# MainPromSignController.net
KiCad netlist of a schematic drawn in EAGLE
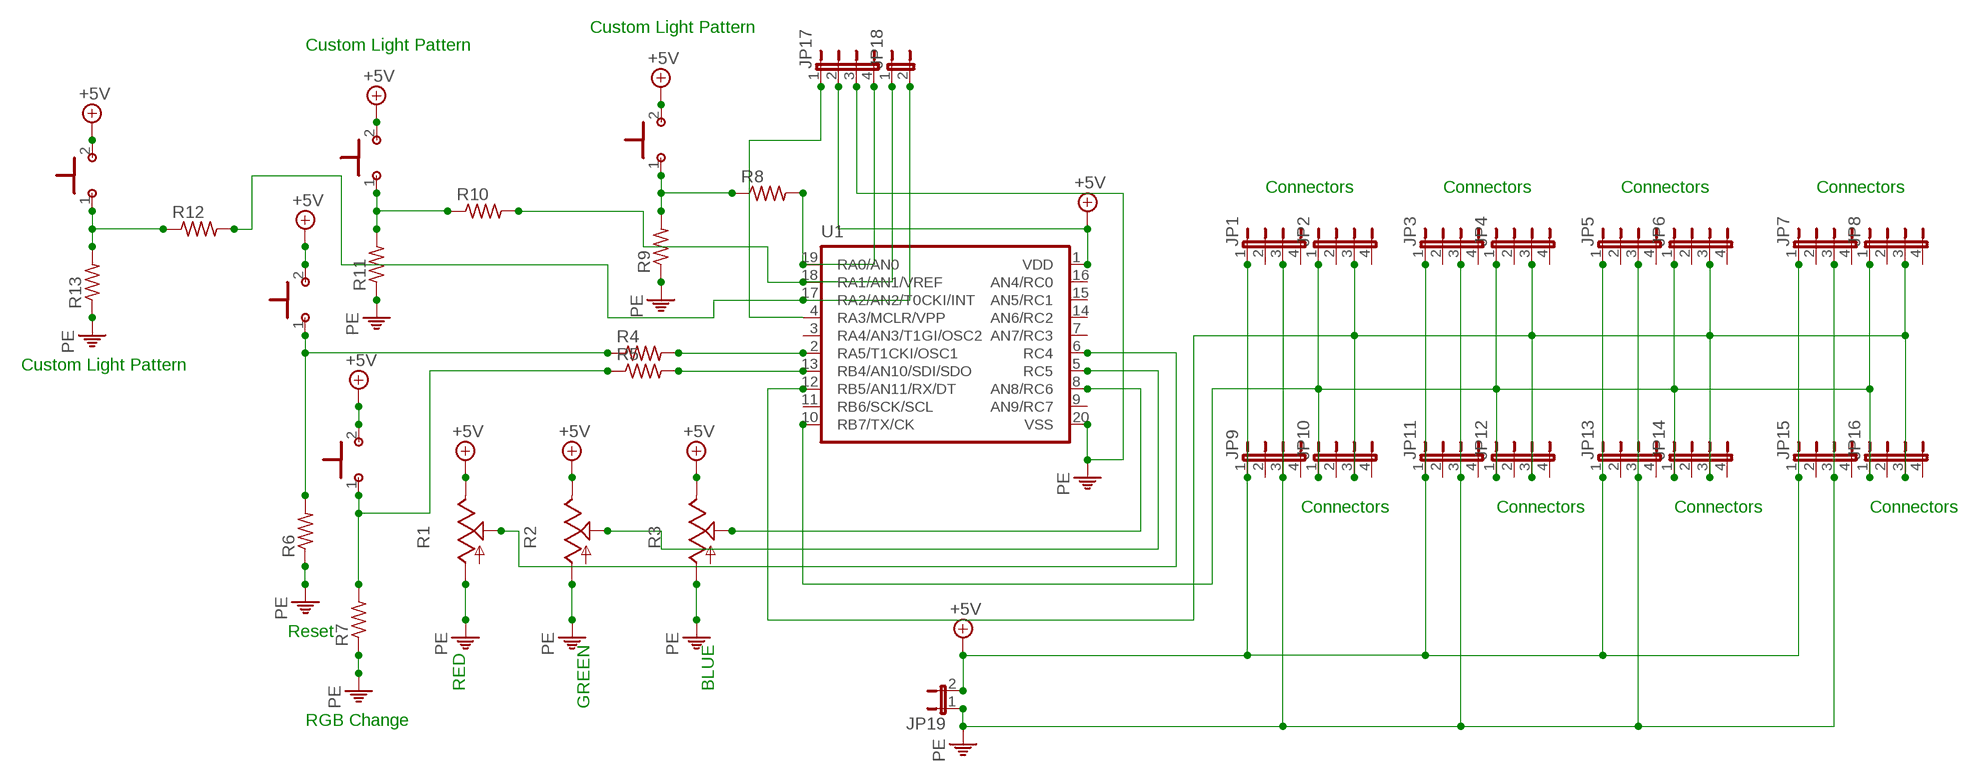
[diagram p0: schematic, sheet 1]

(export (version "E")
  (design (tool "Eeschema 10.0.6"))
  (components
    (comp (ref "JP1")
      (value "JP4E")
      (footprint "eagle-import:JP4")
      (libsource (lib "eagle-import") (part "JP4E"))
    )
    (comp (ref "JP2")
      (value "JP4E")
      (footprint "eagle-import:JP4")
      (libsource (lib "eagle-import") (part "JP4E"))
    )
    (comp (ref "JP3")
      (value "JP4E")
      (footprint "eagle-import:JP4")
      (libsource (lib "eagle-import") (part "JP4E"))
    )
    (comp (ref "JP4")
      (value "JP4E")
      (footprint "eagle-import:JP4")
      (libsource (lib "eagle-import") (part "JP4E"))
    )
    (comp (ref "JP5")
      (value "JP4E")
      (footprint "eagle-import:JP4")
      (libsource (lib "eagle-import") (part "JP4E"))
    )
    (comp (ref "JP6")
      (value "JP4E")
      (footprint "eagle-import:JP4")
      (libsource (lib "eagle-import") (part "JP4E"))
    )
    (comp (ref "JP7")
      (value "JP4E")
      (footprint "eagle-import:JP4")
      (libsource (lib "eagle-import") (part "JP4E"))
    )
    (comp (ref "JP8")
      (value "JP4E")
      (footprint "eagle-import:JP4")
      (libsource (lib "eagle-import") (part "JP4E"))
    )
    (comp (ref "JP9")
      (value "JP4E")
      (footprint "eagle-import:JP4")
      (libsource (lib "eagle-import") (part "JP4E"))
    )
    (comp (ref "JP10")
      (value "JP4E")
      (footprint "eagle-import:JP4")
      (libsource (lib "eagle-import") (part "JP4E"))
    )
    (comp (ref "JP11")
      (value "JP4E")
      (footprint "eagle-import:JP4")
      (libsource (lib "eagle-import") (part "JP4E"))
    )
    (comp (ref "JP12")
      (value "JP4E")
      (footprint "eagle-import:JP4")
      (libsource (lib "eagle-import") (part "JP4E"))
    )
    (comp (ref "JP13")
      (value "JP4E")
      (footprint "eagle-import:JP4")
      (libsource (lib "eagle-import") (part "JP4E"))
    )
    (comp (ref "JP14")
      (value "JP4E")
      (footprint "eagle-import:JP4")
      (libsource (lib "eagle-import") (part "JP4E"))
    )
    (comp (ref "JP15")
      (value "JP4E")
      (footprint "eagle-import:JP4")
      (libsource (lib "eagle-import") (part "JP4E"))
    )
    (comp (ref "JP16")
      (value "JP4E")
      (footprint "eagle-import:JP4")
      (libsource (lib "eagle-import") (part "JP4E"))
    )
    (comp (ref "JP17")
      (value "JP4E")
      (footprint "eagle-import:JP4")
      (libsource (lib "eagle-import") (part "JP4E"))
    )
    (comp (ref "JP18")
      (value "JP1E")
      (footprint "eagle-import:JP1")
      (libsource (lib "eagle-import") (part "JP1E"))
    )
    (comp (ref "JP19")
      (value "JP1E")
      (footprint "eagle-import:JP1")
      (libsource (lib "eagle-import") (part "JP1E"))
    )
    (comp (ref "R1")
      (value "TRIM_US-B25P")
      (footprint "eagle-import:B25P")
      (libsource (lib "eagle-import") (part "TRIM_US-B25P"))
    )
    (comp (ref "R2")
      (value "TRIM_US-B25P")
      (footprint "eagle-import:B25P")
      (libsource (lib "eagle-import") (part "TRIM_US-B25P"))
    )
    (comp (ref "R3")
      (value "TRIM_US-B25P")
      (footprint "eagle-import:B25P")
      (libsource (lib "eagle-import") (part "TRIM_US-B25P"))
    )
    (comp (ref "R4")
      (value "R-US_0207/10")
      (footprint "eagle-import:0207_10")
      (libsource (lib "eagle-import") (part "R-US_0207/10"))
    )
    (comp (ref "R5")
      (value "R-US_0207/10")
      (footprint "eagle-import:0207_10")
      (libsource (lib "eagle-import") (part "R-US_0207/10"))
    )
    (comp (ref "R6")
      (value "R-US_0207/10")
      (footprint "eagle-import:0207_10")
      (libsource (lib "eagle-import") (part "R-US_0207/10"))
    )
    (comp (ref "R7")
      (value "R-US_0207/10")
      (footprint "eagle-import:0207_10")
      (libsource (lib "eagle-import") (part "R-US_0207/10"))
    )
    (comp (ref "R8")
      (value "R-US_0207/10")
      (footprint "eagle-import:0207_10")
      (libsource (lib "eagle-import") (part "R-US_0207/10"))
    )
    (comp (ref "R9")
      (value "R-US_0207/10")
      (footprint "eagle-import:0207_10")
      (libsource (lib "eagle-import") (part "R-US_0207/10"))
    )
    (comp (ref "R10")
      (value "R-US_0207/10")
      (footprint "eagle-import:0207_10")
      (libsource (lib "eagle-import") (part "R-US_0207/10"))
    )
    (comp (ref "R11")
      (value "R-US_0207/10")
      (footprint "eagle-import:0207_10")
      (libsource (lib "eagle-import") (part "R-US_0207/10"))
    )
    (comp (ref "R12")
      (value "R-US_0207/10")
      (footprint "eagle-import:0207_10")
      (libsource (lib "eagle-import") (part "R-US_0207/10"))
    )
    (comp (ref "R13")
      (value "R-US_0207/10")
      (footprint "eagle-import:0207_10")
      (libsource (lib "eagle-import") (part "R-US_0207/10"))
    )
    (comp (ref "U$1")
      (value "PUSHBUTTON")
      (footprint "eagle-import:PUSHBUTTON")
      (libsource (lib "eagle-import") (part "PUSHBUTTON"))
    )
    (comp (ref "U$2")
      (value "PUSHBUTTON")
      (footprint "eagle-import:PUSHBUTTON")
      (libsource (lib "eagle-import") (part "PUSHBUTTON"))
    )
    (comp (ref "U$3")
      (value "PUSHBUTTON")
      (footprint "eagle-import:PUSHBUTTON")
      (libsource (lib "eagle-import") (part "PUSHBUTTON"))
    )
    (comp (ref "U$4")
      (value "PUSHBUTTON")
      (footprint "eagle-import:PUSHBUTTON")
      (libsource (lib "eagle-import") (part "PUSHBUTTON"))
    )
    (comp (ref "U$5")
      (value "PUSHBUTTON")
      (footprint "eagle-import:PUSHBUTTON")
      (libsource (lib "eagle-import") (part "PUSHBUTTON"))
    )
    (comp (ref "U1")
      (value "PIC16F6XX")
      (footprint "eagle-import:DIL20")
      (libsource (lib "eagle-import") (part "PIC16F6XX"))
    )
  )
  (nets
    (net (code "1") (name "+5V") (class "Default")
      (node (ref "JP1") (pin "1") (pinfunction "1_1") (pintype "passive"))
      (node (ref "JP11") (pin "1") (pinfunction "1_1") (pintype "passive"))
      (node (ref "JP13") (pin "1") (pinfunction "1_1") (pintype "passive"))
      (node (ref "JP15") (pin "1") (pinfunction "1_1") (pintype "passive"))
      (node (ref "JP17") (pin "2") (pinfunction "2_2") (pintype "passive"))
      (node (ref "JP19") (pin "2") (pinfunction "2_2") (pintype "passive"))
      (node (ref "JP3") (pin "1") (pinfunction "1_1") (pintype "passive"))
      (node (ref "JP5") (pin "1") (pinfunction "1_1") (pintype "passive"))
      (node (ref "JP7") (pin "1") (pinfunction "1_1") (pintype "passive"))
      (node (ref "JP9") (pin "1") (pinfunction "1_1") (pintype "passive"))
      (node (ref "R1") (pin "E") (pinfunction "E_E") (pintype "passive"))
      (node (ref "R2") (pin "E") (pinfunction "E_E") (pintype "passive"))
      (node (ref "R3") (pin "E") (pinfunction "E_E") (pintype "passive"))
      (node (ref "U$1") (pin "2") (pinfunction "2_2") (pintype "bidirectional"))
      (node (ref "U$2") (pin "2") (pinfunction "2_2") (pintype "bidirectional"))
      (node (ref "U$3") (pin "2") (pinfunction "2_2") (pintype "bidirectional"))
      (node (ref "U$4") (pin "2") (pinfunction "2_2") (pintype "bidirectional"))
      (node (ref "U$5") (pin "2") (pinfunction "2_2") (pintype "bidirectional"))
      (node (ref "U1") (pin "1") (pinfunction "VDD_1") (pintype "power_in"))
    )
    (net (code "2") (name "Net-(R4-Pad1)") (class "Default")
      (node (ref "R4") (pin "1") (pinfunction "1_1") (pintype "passive"))
      (node (ref "R6") (pin "2") (pinfunction "2_2") (pintype "passive"))
      (node (ref "U$1") (pin "1") (pinfunction "1_1") (pintype "bidirectional"))
    )
    (net (code "3") (name "Net-(R5-Pad1)") (class "Default")
      (node (ref "R5") (pin "1") (pinfunction "1_1") (pintype "passive"))
      (node (ref "R7") (pin "2") (pinfunction "2_2") (pintype "passive"))
      (node (ref "U$2") (pin "1") (pinfunction "1_1") (pintype "bidirectional"))
    )
    (net (code "4") (name "Net-(R8-Pad1)") (class "Default")
      (node (ref "R8") (pin "1") (pinfunction "1_1") (pintype "passive"))
      (node (ref "R9") (pin "2") (pinfunction "2_2") (pintype "passive"))
      (node (ref "U$3") (pin "1") (pinfunction "1_1") (pintype "bidirectional"))
    )
    (net (code "5") (name "Net-(R10-Pad1)") (class "Default")
      (node (ref "R10") (pin "1") (pinfunction "1_1") (pintype "passive"))
      (node (ref "R11") (pin "2") (pinfunction "2_2") (pintype "passive"))
      (node (ref "U$4") (pin "1") (pinfunction "1_1") (pintype "bidirectional"))
    )
    (net (code "6") (name "Net-(R12-Pad1)") (class "Default")
      (node (ref "R12") (pin "1") (pinfunction "1_1") (pintype "passive"))
      (node (ref "R13") (pin "2") (pinfunction "2_2") (pintype "passive"))
      (node (ref "U$5") (pin "1") (pinfunction "1_1") (pintype "bidirectional"))
    )
    (net (code "7") (name "Net-(U1-AN8{slash}RC6)") (class "Default")
      (node (ref "R3") (pin "S") (pinfunction "S_S") (pintype "passive"))
      (node (ref "U1") (pin "8") (pinfunction "AN8/RC6_8") (pintype "bidirectional"))
    )
    (net (code "8") (name "Net-(U1-RA0{slash}AN0)") (class "Default")
      (node (ref "JP17") (pin "4") (pinfunction "4_4") (pintype "passive"))
      (node (ref "R8") (pin "2") (pinfunction "2_2") (pintype "passive"))
      (node (ref "U1") (pin "19") (pinfunction "RA0/AN0_19") (pintype "bidirectional"))
    )
    (net (code "9") (name "Net-(U1-RA1{slash}AN1{slash}VREF)") (class "Default")
      (node (ref "JP18") (pin "1") (pinfunction "1_1") (pintype "passive"))
      (node (ref "R10") (pin "2") (pinfunction "2_2") (pintype "passive"))
      (node (ref "U1") (pin "18") (pinfunction "RA1/AN1/VREF_18") (pintype "bidirectional"))
    )
    (net (code "10") (name "Net-(U1-RA2{slash}AN2{slash}T0CKI{slash}INT)") (class "Default")
      (node (ref "JP18") (pin "2") (pinfunction "2_2") (pintype "passive"))
      (node (ref "R12") (pin "2") (pinfunction "2_2") (pintype "passive"))
      (node (ref "U1") (pin "17") (pinfunction "RA2/AN2/T0CKI/INT_17") (pintype "bidirectional"))
    )
    (net (code "11") (name "Net-(U1-RA3{slash}MCLR{slash}VPP)") (class "Default")
      (node (ref "JP17") (pin "1") (pinfunction "1_1") (pintype "passive"))
      (node (ref "U1") (pin "4") (pinfunction "RA3/MCLR/VPP_4") (pintype "input"))
    )
    (net (code "12") (name "Net-(U1-RA5{slash}T1CKI{slash}OSC1)") (class "Default")
      (node (ref "R4") (pin "2") (pinfunction "2_2") (pintype "passive"))
      (node (ref "U1") (pin "2") (pinfunction "RA5/T1CKI/OSC1_2") (pintype "bidirectional"))
    )
    (net (code "13") (name "Net-(U1-RB4{slash}AN10{slash}SDI{slash}SDO)") (class "Default")
      (node (ref "R5") (pin "2") (pinfunction "2_2") (pintype "passive"))
      (node (ref "U1") (pin "13") (pinfunction "RB4/AN10/SDI/SDO_13") (pintype "bidirectional"))
    )
    (net (code "14") (name "Net-(U1-RB5{slash}AN11{slash}RX{slash}DT)") (class "Default")
      (node (ref "JP10") (pin "3") (pinfunction "3_3") (pintype "passive"))
      (node (ref "JP12") (pin "3") (pinfunction "3_3") (pintype "passive"))
      (node (ref "JP14") (pin "3") (pinfunction "3_3") (pintype "passive"))
      (node (ref "JP16") (pin "3") (pinfunction "3_3") (pintype "passive"))
      (node (ref "JP2") (pin "3") (pinfunction "3_3") (pintype "passive"))
      (node (ref "JP4") (pin "3") (pinfunction "3_3") (pintype "passive"))
      (node (ref "JP6") (pin "3") (pinfunction "3_3") (pintype "passive"))
      (node (ref "JP8") (pin "3") (pinfunction "3_3") (pintype "passive"))
      (node (ref "U1") (pin "12") (pinfunction "RB5/AN11/RX/DT_12") (pintype "bidirectional"))
    )
    (net (code "15") (name "Net-(U1-RB7{slash}TX{slash}CK)") (class "Default")
      (node (ref "JP10") (pin "1") (pinfunction "1_1") (pintype "passive"))
      (node (ref "JP12") (pin "1") (pinfunction "1_1") (pintype "passive"))
      (node (ref "JP14") (pin "1") (pinfunction "1_1") (pintype "passive"))
      (node (ref "JP16") (pin "1") (pinfunction "1_1") (pintype "passive"))
      (node (ref "JP2") (pin "1") (pinfunction "1_1") (pintype "passive"))
      (node (ref "JP4") (pin "1") (pinfunction "1_1") (pintype "passive"))
      (node (ref "JP6") (pin "1") (pinfunction "1_1") (pintype "passive"))
      (node (ref "JP8") (pin "1") (pinfunction "1_1") (pintype "passive"))
      (node (ref "U1") (pin "10") (pinfunction "RB7/TX/CK_10") (pintype "bidirectional"))
    )
    (net (code "16") (name "Net-(U1-RC4)") (class "Default")
      (node (ref "R1") (pin "S") (pinfunction "S_S") (pintype "passive"))
      (node (ref "U1") (pin "6") (pinfunction "RC4_6") (pintype "bidirectional"))
    )
    (net (code "17") (name "Net-(U1-RC5)") (class "Default")
      (node (ref "R2") (pin "S") (pinfunction "S_S") (pintype "passive"))
      (node (ref "U1") (pin "5") (pinfunction "RC5_5") (pintype "bidirectional"))
    )
    (net (code "18") (name "PE") (class "Default")
      (node (ref "JP1") (pin "3") (pinfunction "3_3") (pintype "passive"))
      (node (ref "JP11") (pin "3") (pinfunction "3_3") (pintype "passive"))
      (node (ref "JP13") (pin "3") (pinfunction "3_3") (pintype "passive"))
      (node (ref "JP15") (pin "3") (pinfunction "3_3") (pintype "passive"))
      (node (ref "JP17") (pin "3") (pinfunction "3_3") (pintype "passive"))
      (node (ref "JP19") (pin "1") (pinfunction "1_1") (pintype "passive"))
      (node (ref "JP3") (pin "3") (pinfunction "3_3") (pintype "passive"))
      (node (ref "JP5") (pin "3") (pinfunction "3_3") (pintype "passive"))
      (node (ref "JP7") (pin "3") (pinfunction "3_3") (pintype "passive"))
      (node (ref "JP9") (pin "3") (pinfunction "3_3") (pintype "passive"))
      (node (ref "R1") (pin "A") (pinfunction "A_A") (pintype "passive"))
      (node (ref "R11") (pin "1") (pinfunction "1_1") (pintype "passive"))
      (node (ref "R13") (pin "1") (pinfunction "1_1") (pintype "passive"))
      (node (ref "R2") (pin "A") (pinfunction "A_A") (pintype "passive"))
      (node (ref "R3") (pin "A") (pinfunction "A_A") (pintype "passive"))
      (node (ref "R6") (pin "1") (pinfunction "1_1") (pintype "passive"))
      (node (ref "R7") (pin "1") (pinfunction "1_1") (pintype "passive"))
      (node (ref "R9") (pin "1") (pinfunction "1_1") (pintype "passive"))
      (node (ref "U1") (pin "20") (pinfunction "VSS_20") (pintype "power_in"))
    )
    (net (code "19") (name "unconnected-(JP1-Pad2)") (class "Default")
      (node (ref "JP1") (pin "2") (pinfunction "2_2") (pintype "passive"))
    )
    (net (code "20") (name "unconnected-(JP1-Pad4)") (class "Default")
      (node (ref "JP1") (pin "4") (pinfunction "4_4") (pintype "passive"))
    )
    (net (code "21") (name "unconnected-(JP2-Pad2)") (class "Default")
      (node (ref "JP2") (pin "2") (pinfunction "2_2") (pintype "passive"))
    )
    (net (code "22") (name "unconnected-(JP2-Pad4)") (class "Default")
      (node (ref "JP2") (pin "4") (pinfunction "4_4") (pintype "passive"))
    )
    (net (code "23") (name "unconnected-(JP3-Pad2)") (class "Default")
      (node (ref "JP3") (pin "2") (pinfunction "2_2") (pintype "passive"))
    )
    (net (code "24") (name "unconnected-(JP3-Pad4)") (class "Default")
      (node (ref "JP3") (pin "4") (pinfunction "4_4") (pintype "passive"))
    )
    (net (code "25") (name "unconnected-(JP4-Pad2)") (class "Default")
      (node (ref "JP4") (pin "2") (pinfunction "2_2") (pintype "passive"))
    )
    (net (code "26") (name "unconnected-(JP4-Pad4)") (class "Default")
      (node (ref "JP4") (pin "4") (pinfunction "4_4") (pintype "passive"))
    )
    (net (code "27") (name "unconnected-(JP5-Pad2)") (class "Default")
      (node (ref "JP5") (pin "2") (pinfunction "2_2") (pintype "passive"))
    )
    (net (code "28") (name "unconnected-(JP5-Pad4)") (class "Default")
      (node (ref "JP5") (pin "4") (pinfunction "4_4") (pintype "passive"))
    )
    (net (code "29") (name "unconnected-(JP6-Pad2)") (class "Default")
      (node (ref "JP6") (pin "2") (pinfunction "2_2") (pintype "passive"))
    )
    (net (code "30") (name "unconnected-(JP6-Pad4)") (class "Default")
      (node (ref "JP6") (pin "4") (pinfunction "4_4") (pintype "passive"))
    )
    (net (code "31") (name "unconnected-(JP7-Pad2)") (class "Default")
      (node (ref "JP7") (pin "2") (pinfunction "2_2") (pintype "passive"))
    )
    (net (code "32") (name "unconnected-(JP7-Pad4)") (class "Default")
      (node (ref "JP7") (pin "4") (pinfunction "4_4") (pintype "passive"))
    )
    (net (code "33") (name "unconnected-(JP8-Pad2)") (class "Default")
      (node (ref "JP8") (pin "2") (pinfunction "2_2") (pintype "passive"))
    )
    (net (code "34") (name "unconnected-(JP8-Pad4)") (class "Default")
      (node (ref "JP8") (pin "4") (pinfunction "4_4") (pintype "passive"))
    )
    (net (code "35") (name "unconnected-(JP9-Pad2)") (class "Default")
      (node (ref "JP9") (pin "2") (pinfunction "2_2") (pintype "passive"))
    )
    (net (code "36") (name "unconnected-(JP9-Pad4)") (class "Default")
      (node (ref "JP9") (pin "4") (pinfunction "4_4") (pintype "passive"))
    )
    (net (code "37") (name "unconnected-(JP10-Pad2)") (class "Default")
      (node (ref "JP10") (pin "2") (pinfunction "2_2") (pintype "passive"))
    )
    (net (code "38") (name "unconnected-(JP10-Pad4)") (class "Default")
      (node (ref "JP10") (pin "4") (pinfunction "4_4") (pintype "passive"))
    )
    (net (code "39") (name "unconnected-(JP11-Pad2)") (class "Default")
      (node (ref "JP11") (pin "2") (pinfunction "2_2") (pintype "passive"))
    )
    (net (code "40") (name "unconnected-(JP11-Pad4)") (class "Default")
      (node (ref "JP11") (pin "4") (pinfunction "4_4") (pintype "passive"))
    )
    (net (code "41") (name "unconnected-(JP12-Pad2)") (class "Default")
      (node (ref "JP12") (pin "2") (pinfunction "2_2") (pintype "passive"))
    )
    (net (code "42") (name "unconnected-(JP12-Pad4)") (class "Default")
      (node (ref "JP12") (pin "4") (pinfunction "4_4") (pintype "passive"))
    )
    (net (code "43") (name "unconnected-(JP13-Pad2)") (class "Default")
      (node (ref "JP13") (pin "2") (pinfunction "2_2") (pintype "passive"))
    )
    (net (code "44") (name "unconnected-(JP13-Pad4)") (class "Default")
      (node (ref "JP13") (pin "4") (pinfunction "4_4") (pintype "passive"))
    )
    (net (code "45") (name "unconnected-(JP14-Pad2)") (class "Default")
      (node (ref "JP14") (pin "2") (pinfunction "2_2") (pintype "passive"))
    )
    (net (code "46") (name "unconnected-(JP14-Pad4)") (class "Default")
      (node (ref "JP14") (pin "4") (pinfunction "4_4") (pintype "passive"))
    )
    (net (code "47") (name "unconnected-(JP15-Pad2)") (class "Default")
      (node (ref "JP15") (pin "2") (pinfunction "2_2") (pintype "passive"))
    )
    (net (code "48") (name "unconnected-(JP15-Pad4)") (class "Default")
      (node (ref "JP15") (pin "4") (pinfunction "4_4") (pintype "passive"))
    )
    (net (code "49") (name "unconnected-(JP16-Pad2)") (class "Default")
      (node (ref "JP16") (pin "2") (pinfunction "2_2") (pintype "passive"))
    )
    (net (code "50") (name "unconnected-(JP16-Pad4)") (class "Default")
      (node (ref "JP16") (pin "4") (pinfunction "4_4") (pintype "passive"))
    )
    (net (code "51") (name "unconnected-(U1-AN4{slash}RC0-Pad16)") (class "Default")
      (node (ref "U1") (pin "16") (pinfunction "AN4/RC0_16") (pintype "bidirectional"))
    )
    (net (code "52") (name "unconnected-(U1-AN5{slash}RC1-Pad15)") (class "Default")
      (node (ref "U1") (pin "15") (pinfunction "AN5/RC1_15") (pintype "bidirectional"))
    )
    (net (code "53") (name "unconnected-(U1-AN6{slash}RC2-Pad14)") (class "Default")
      (node (ref "U1") (pin "14") (pinfunction "AN6/RC2_14") (pintype "bidirectional"))
    )
    (net (code "54") (name "unconnected-(U1-AN7{slash}RC3-Pad7)") (class "Default")
      (node (ref "U1") (pin "7") (pinfunction "AN7/RC3_7") (pintype "bidirectional"))
    )
    (net (code "55") (name "unconnected-(U1-AN9{slash}RC7-Pad9)") (class "Default")
      (node (ref "U1") (pin "9") (pinfunction "AN9/RC7_9") (pintype "bidirectional"))
    )
    (net (code "56") (name "unconnected-(U1-RA4{slash}AN3{slash}T1GI{slash}OSC2-Pad3)") (class "Default")
      (node (ref "U1") (pin "3") (pinfunction "RA4/AN3/T1GI/OSC2_3") (pintype "bidirectional"))
    )
    (net (code "57") (name "unconnected-(U1-RB6{slash}SCK{slash}SCL-Pad11)") (class "Default")
      (node (ref "U1") (pin "11") (pinfunction "RB6/SCK/SCL_11") (pintype "bidirectional"))
    )
  )
)
